# schematicNewNoNull.net
KiCad netlist of a schematic drawn in EAGLE
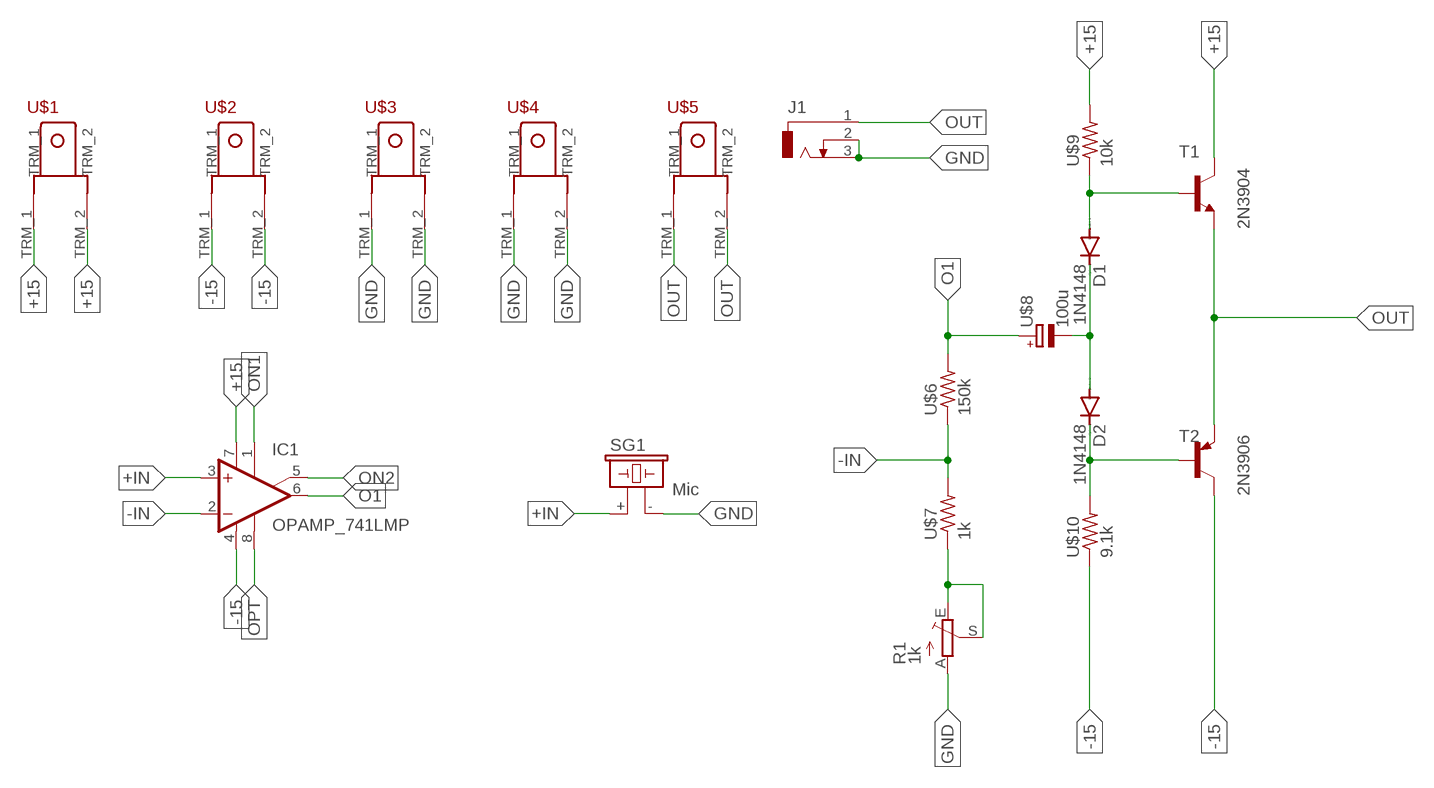
[diagram p0: schematic, sheet 1]

(export (version "E")
  (design (tool "Eeschema 10.0.6"))
  (components
    (comp (ref "D1")
      (value "1N4148")
      (footprint "eagle-import:DO35-10")
      (libsource (lib "eagle-import") (part "1N4148DO35-10"))
    )
    (comp (ref "D2")
      (value "1N4148")
      (footprint "eagle-import:DO35-10")
      (libsource (lib "eagle-import") (part "1N4148DO35-10"))
    )
    (comp (ref "IC1")
      (value "OPAMP_741LMP")
      (footprint "eagle-import:DIL08")
      (libsource (lib "eagle-import") (part "OPAMP_741PLM"))
    )
    (comp (ref "J1")
      (value "CON_JACK")
      (footprint "eagle-import:DCJ0303")
      (libsource (lib "eagle-import") (part "CON_JACK"))
    )
    (comp (ref "R1")
      (value "1k")
      (footprint "eagle-import:CA6V")
      (libsource (lib "eagle-import") (part "TRIM_EU-CA6V"))
    )
    (comp (ref "SG1")
      (value "Mic")
      (footprint "eagle-import:F_CM12P")
      (libsource (lib "eagle-import") (part "BUZZER"))
    )
    (comp (ref "T1")
      (value "2N3904")
      (footprint "eagle-import:TO92-EBC")
      (libsource (lib "eagle-import") (part "-NPN-TO92-EBC2N3904"))
    )
    (comp (ref "T2")
      (value "2N3906")
      (footprint "eagle-import:TO92-EBC")
      (libsource (lib "eagle-import") (part "-PNP-TO92-EBC2N3906"))
    )
    (comp (ref "U$1")
      (value "TERMINAL_EDITED")
      (footprint "eagle-import:TERMINAL_EDITED")
      (libsource (lib "eagle-import") (part "TERMINAL_EDITED"))
    )
    (comp (ref "U$2")
      (value "TERMINAL_EDITED")
      (footprint "eagle-import:TERMINAL_EDITED")
      (libsource (lib "eagle-import") (part "TERMINAL_EDITED"))
    )
    (comp (ref "U$3")
      (value "TERMINAL_EDITED")
      (footprint "eagle-import:TERMINAL_EDITED")
      (libsource (lib "eagle-import") (part "TERMINAL_EDITED"))
    )
    (comp (ref "U$4")
      (value "TERMINAL_EDITED")
      (footprint "eagle-import:TERMINAL_EDITED")
      (libsource (lib "eagle-import") (part "TERMINAL_EDITED"))
    )
    (comp (ref "U$5")
      (value "TERMINAL_EDITED")
      (footprint "eagle-import:TERMINAL_EDITED")
      (libsource (lib "eagle-import") (part "TERMINAL_EDITED"))
    )
    (comp (ref "U$6")
      (value "150k")
      (footprint "eagle-import:0204_7")
      (libsource (lib "eagle-import") (part "RES-7"))
    )
    (comp (ref "U$7")
      (value "1k")
      (footprint "eagle-import:0204_7")
      (libsource (lib "eagle-import") (part "RES-7"))
    )
    (comp (ref "U$8")
      (value "100u")
      (footprint "eagle-import:E3,5-8")
      (libsource (lib "eagle-import") (part "CAP_POL"))
    )
    (comp (ref "U$9")
      (value "10k")
      (footprint "eagle-import:0204_7")
      (libsource (lib "eagle-import") (part "RES-7"))
    )
    (comp (ref "U$10")
      (value "9.1k")
      (footprint "eagle-import:0204_7")
      (libsource (lib "eagle-import") (part "RES-7"))
    )
  )
  (nets
    (net (code "1") (name "+15") (class "Default")
      (node (ref "IC1") (pin "7") (pinfunction "V+_7") (pintype "power_in"))
      (node (ref "T1") (pin "C") (pinfunction "C_C") (pintype "passive"))
      (node (ref "U$1") (pin "TRM_1") (pinfunction "TRM_1_TRM_1") (pintype "bidirectional"))
      (node (ref "U$1") (pin "TRM_2") (pinfunction "TRM_2_TRM_2") (pintype "bidirectional"))
      (node (ref "U$9") (pin "2") (pinfunction "2_2") (pintype "passive"))
    )
    (net (code "2") (name "+IN") (class "Default")
      (node (ref "IC1") (pin "3") (pinfunction "+IN_3") (pintype "input"))
      (node (ref "SG1") (pin "+") (pinfunction "1_+") (pintype "passive"))
    )
    (net (code "3") (name "-15") (class "Default")
      (node (ref "IC1") (pin "4") (pinfunction "V-_4") (pintype "power_in"))
      (node (ref "T2") (pin "C") (pinfunction "C_C") (pintype "passive"))
      (node (ref "U$10") (pin "1") (pinfunction "1_1") (pintype "passive"))
      (node (ref "U$2") (pin "TRM_1") (pinfunction "TRM_1_TRM_1") (pintype "bidirectional"))
      (node (ref "U$2") (pin "TRM_2") (pinfunction "TRM_2_TRM_2") (pintype "bidirectional"))
    )
    (net (code "4") (name "-IN") (class "Default")
      (node (ref "IC1") (pin "2") (pinfunction "-IN_2") (pintype "input"))
      (node (ref "U$6") (pin "1") (pinfunction "1_1") (pintype "passive"))
      (node (ref "U$7") (pin "2") (pinfunction "2_2") (pintype "passive"))
    )
    (net (code "5") (name "GND") (class "Default")
      (node (ref "J1") (pin "2") (pinfunction "2_2") (pintype "passive"))
      (node (ref "J1") (pin "3") (pinfunction "3_3") (pintype "passive"))
      (node (ref "R1") (pin "A") (pinfunction "A_A") (pintype "passive"))
      (node (ref "SG1") (pin "-") (pinfunction "2_-") (pintype "passive"))
      (node (ref "U$3") (pin "TRM_1") (pinfunction "TRM_1_TRM_1") (pintype "bidirectional"))
      (node (ref "U$3") (pin "TRM_2") (pinfunction "TRM_2_TRM_2") (pintype "bidirectional"))
      (node (ref "U$4") (pin "TRM_1") (pinfunction "TRM_1_TRM_1") (pintype "bidirectional"))
      (node (ref "U$4") (pin "TRM_2") (pinfunction "TRM_2_TRM_2") (pintype "bidirectional"))
    )
    (net (code "6") (name "Net-(D1-PadA)") (class "Default")
      (node (ref "D1") (pin "A") (pinfunction "A_A") (pintype "passive"))
      (node (ref "T1") (pin "B") (pinfunction "B_B") (pintype "passive"))
      (node (ref "U$9") (pin "1") (pinfunction "1_1") (pintype "passive"))
    )
    (net (code "7") (name "Net-(D1-PadC)") (class "Default")
      (node (ref "D1") (pin "C") (pinfunction "C_C") (pintype "passive"))
      (node (ref "D2") (pin "A") (pinfunction "A_A") (pintype "passive"))
      (node (ref "U$8") (pin "-") (pinfunction "-_-") (pintype "passive"))
    )
    (net (code "8") (name "Net-(D2-PadC)") (class "Default")
      (node (ref "D2") (pin "C") (pinfunction "C_C") (pintype "passive"))
      (node (ref "T2") (pin "B") (pinfunction "B_B") (pintype "passive"))
      (node (ref "U$10") (pin "2") (pinfunction "2_2") (pintype "passive"))
    )
    (net (code "9") (name "Net-(R1-PadE)") (class "Default")
      (node (ref "R1") (pin "E") (pinfunction "E_E") (pintype "passive"))
      (node (ref "R1") (pin "S") (pinfunction "S_S") (pintype "passive"))
      (node (ref "U$7") (pin "1") (pinfunction "1_1") (pintype "passive"))
    )
    (net (code "10") (name "O1") (class "Default")
      (node (ref "IC1") (pin "6") (pinfunction "OUT_6") (pintype "output"))
      (node (ref "U$6") (pin "2") (pinfunction "2_2") (pintype "passive"))
      (node (ref "U$8") (pin "+") (pinfunction "+_+") (pintype "passive"))
    )
    (net (code "11") (name "ON1") (class "Default")
      (node (ref "IC1") (pin "1") (pinfunction "ON1_1") (pintype "passive"))
    )
    (net (code "12") (name "ON2") (class "Default")
      (node (ref "IC1") (pin "5") (pinfunction "ON2_5") (pintype "passive"))
    )
    (net (code "13") (name "OPT") (class "Default")
      (node (ref "IC1") (pin "8") (pinfunction "OPT_8") (pintype "passive"))
    )
    (net (code "14") (name "OUT") (class "Default")
      (node (ref "J1") (pin "1") (pinfunction "1_1") (pintype "passive"))
      (node (ref "T1") (pin "E") (pinfunction "E_E") (pintype "passive"))
      (node (ref "T2") (pin "E") (pinfunction "E_E") (pintype "passive"))
      (node (ref "U$5") (pin "TRM_1") (pinfunction "TRM_1_TRM_1") (pintype "bidirectional"))
      (node (ref "U$5") (pin "TRM_2") (pinfunction "TRM_2_TRM_2") (pintype "bidirectional"))
    )
  )
)
